# jncc3000.net
KiCad netlist of a schematic drawn in EAGLE
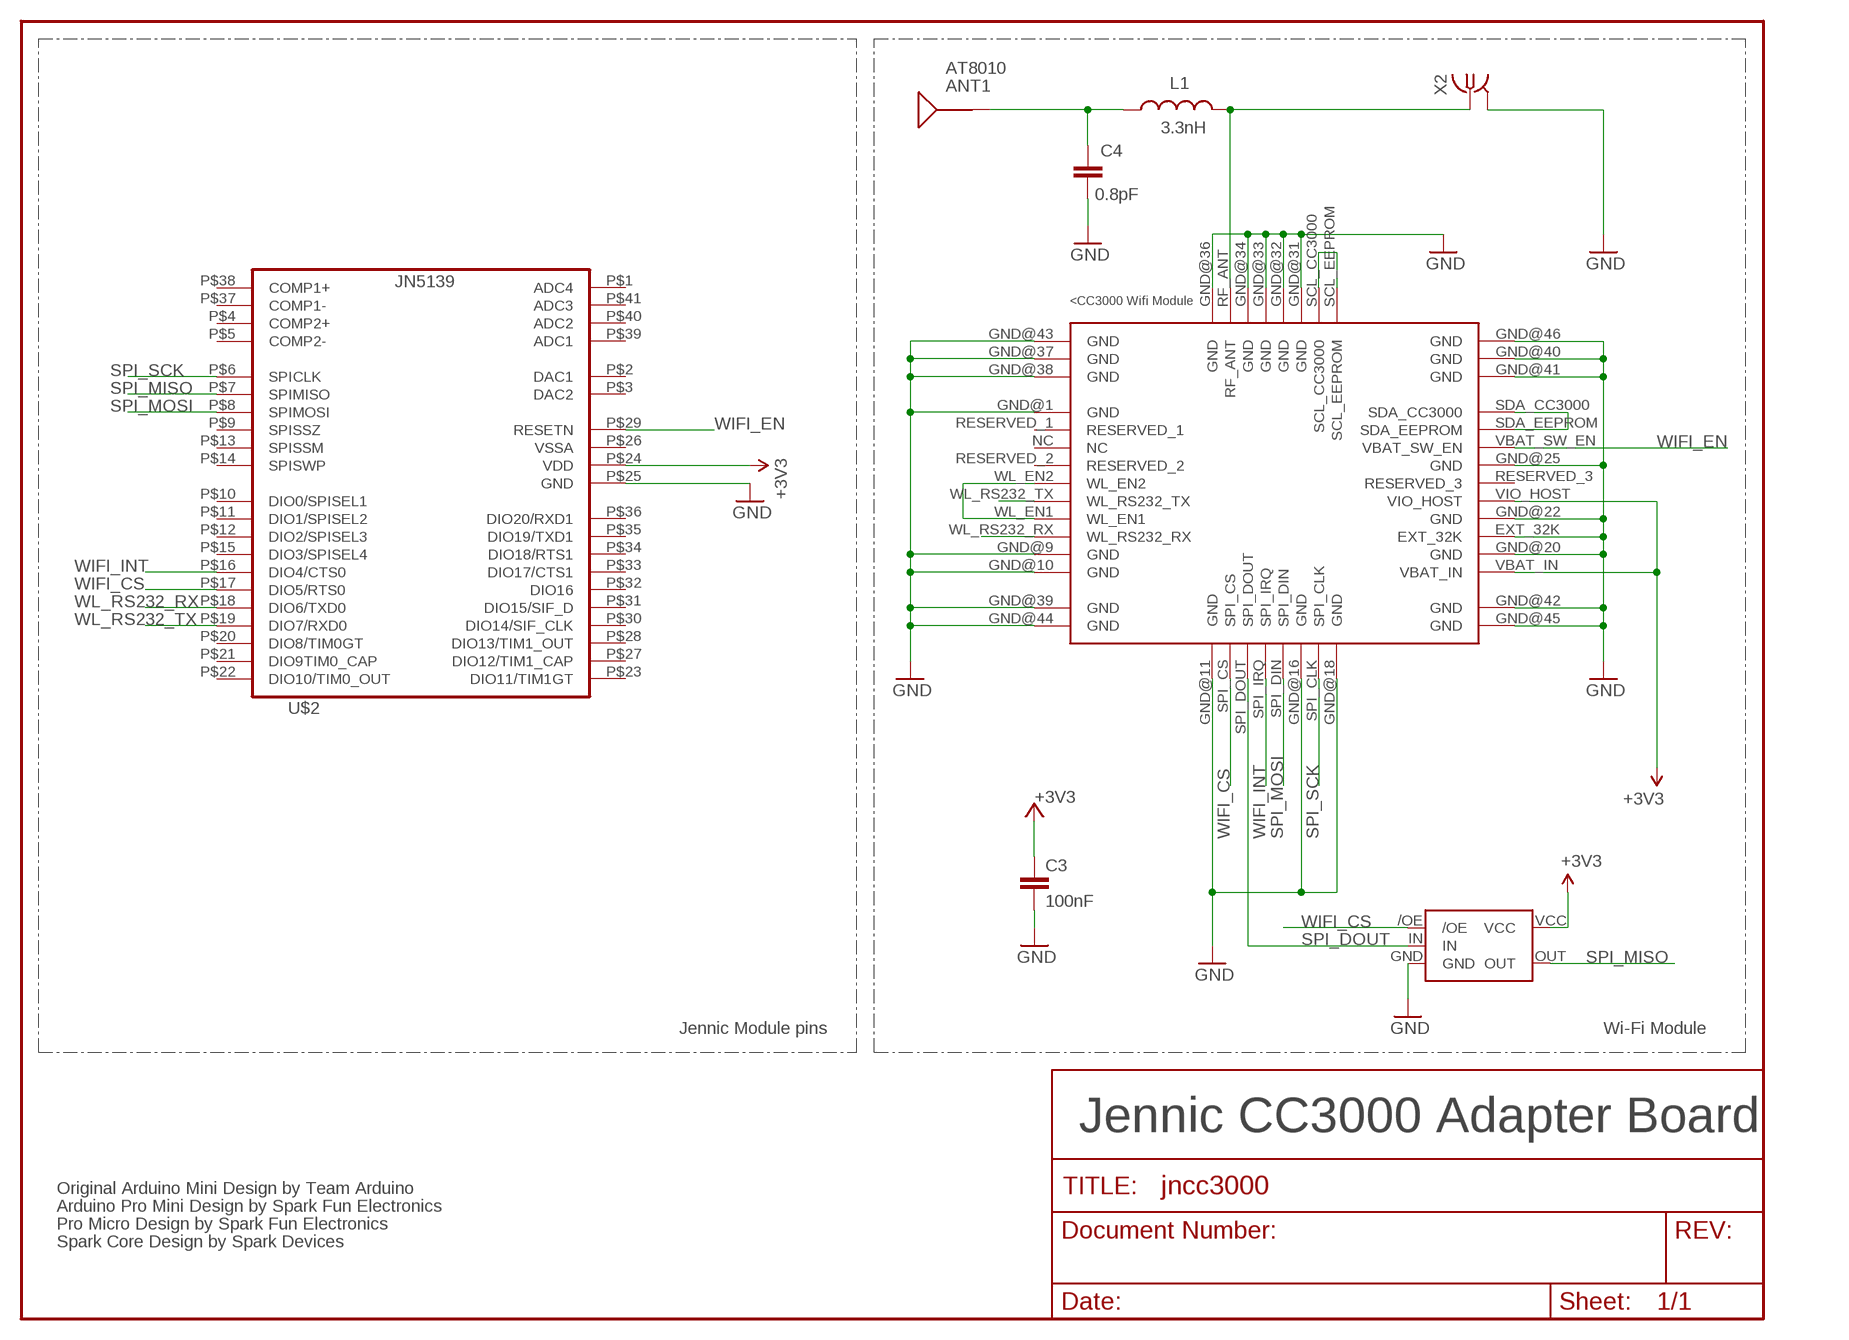
[diagram p0: schematic, sheet 1]

(export (version "E")
  (design (tool "Eeschema 10.0.6"))
  (components
    (comp (ref "ANT1")
      (value "AT8010")
      (footprint "eagle-import:AT8010")
      (libsource (lib "eagle-import") (part "AT8010"))
    )
    (comp (ref "C3")
      (value "100nF")
      (footprint "eagle-import:C0603")
      (libsource (lib "eagle-import") (part "C-EUC0603"))
    )
    (comp (ref "C4")
      (value "0.8pF")
      (footprint "eagle-import:C0603")
      (fields (field (name "COMMENT") "RF Capacitor"))
      (libsource (lib "eagle-import") (part "C-EUC0603"))
    )
    (comp (ref "L1")
      (value "3.3nH")
      (footprint "eagle-import:0603")
      (fields (field (name "COMMENT") "RF Inductor"))
      (libsource (lib "eagle-import") (part "INDUCTOR0603"))
    )
    (comp (ref "U$2")
      (value "JENNIC_JN51XXTH")
      (footprint "eagle-import:JN5139_TH")
      (libsource (lib "eagle-import") (part "JENNIC_JN51XXTH"))
    )
    (comp (ref "U1")
      (value "CC3000")
      (footprint "eagle-import:CC3000")
      (libsource (lib "eagle-import") (part "CC3000"))
    )
    (comp (ref "U4")
      (value "NL17SZ125SOT553")
      (footprint "eagle-import:SOT-553")
      (libsource (lib "eagle-import") (part "NL17SZ125SOT553"))
    )
    (comp (ref "X2")
      (value "IPEX-20279-001E")
      (footprint "eagle-import:IPEX-20279-001E")
      (libsource (lib "eagle-import") (part "IPEX-20279-001E"))
    )
  )
  (nets
    (net (code "1") (name "+3V3") (class "Default")
      (node (ref "C3") (pin "1") (pinfunction "1_1") (pintype "passive"))
      (node (ref "U$2") (pin "P$24") (pinfunction "VDD_P$24") (pintype "bidirectional"))
      (node (ref "U1") (pin "VBAT_IN") (pinfunction "VBAT_IN_VBAT_IN") (pintype "power_in"))
      (node (ref "U1") (pin "VIO_HOST") (pinfunction "VIO_HOST_VIO_HOST") (pintype "power_in"))
      (node (ref "U4") (pin "VCC") (pinfunction "VCC_VCC") (pintype "bidirectional"))
    )
    (net (code "2") (name "/SPI_DOUT") (class "Default")
      (node (ref "U1") (pin "SPI_DOUT") (pinfunction "SPI_DOUT_SPI_DOUT") (pintype "output"))
      (node (ref "U4") (pin "IN") (pinfunction "IN_IN") (pintype "bidirectional"))
    )
    (net (code "3") (name "/SPI_MISO") (class "Default")
      (node (ref "U$2") (pin "P$7") (pinfunction "SPIMISO_P$7") (pintype "bidirectional"))
      (node (ref "U4") (pin "OUT") (pinfunction "OUT_OUT") (pintype "bidirectional"))
    )
    (net (code "4") (name "/SPI_MOSI") (class "Default")
      (node (ref "U$2") (pin "P$8") (pinfunction "SPIMOSI_P$8") (pintype "bidirectional"))
      (node (ref "U1") (pin "SPI_DIN") (pinfunction "SPI_DIN_SPI_DIN") (pintype "input"))
    )
    (net (code "5") (name "/SPI_SCK") (class "Default")
      (node (ref "U$2") (pin "P$6") (pinfunction "SPICLK_P$6") (pintype "bidirectional"))
      (node (ref "U1") (pin "SPI_CLK") (pinfunction "SPI_CLK_SPI_CLK") (pintype "input"))
    )
    (net (code "6") (name "/WIFI_CS") (class "Default")
      (node (ref "U$2") (pin "P$17") (pinfunction "DIO5/RTS0_P$17") (pintype "bidirectional"))
      (node (ref "U1") (pin "SPI_CS") (pinfunction "SPI_CS_SPI_CS") (pintype "input"))
      (node (ref "U4") (pin "/OE") (pinfunction "/OE_/OE") (pintype "bidirectional"))
    )
    (net (code "7") (name "/WIFI_EN") (class "Default")
      (node (ref "U$2") (pin "P$29") (pinfunction "RESETN_P$29") (pintype "bidirectional"))
      (node (ref "U1") (pin "VBAT_SW_EN") (pinfunction "VBAT_SW_EN_VBAT_SW_EN") (pintype "input"))
    )
    (net (code "8") (name "/WIFI_INT") (class "Default")
      (node (ref "U$2") (pin "P$16") (pinfunction "DIO4/CTS0_P$16") (pintype "bidirectional"))
      (node (ref "U1") (pin "SPI_IRQ") (pinfunction "SPI_IRQ_SPI_IRQ") (pintype "output"))
    )
    (net (code "9") (name "/WL_RS232_RX") (class "Default")
      (node (ref "U$2") (pin "P$18") (pinfunction "DIO6/TXD0_P$18") (pintype "bidirectional"))
      (node (ref "U1") (pin "WL_RS232_RX") (pinfunction "WL_RS232_RX_WL_RS232_RX") (pintype "input"))
    )
    (net (code "10") (name "/WL_RS232_TX") (class "Default")
      (node (ref "U$2") (pin "P$19") (pinfunction "DIO7/RXD0_P$19") (pintype "bidirectional"))
      (node (ref "U1") (pin "WL_RS232_TX") (pinfunction "WL_RS232_TX_WL_RS232_TX") (pintype "output"))
    )
    (net (code "11") (name "GND") (class "Default")
      (node (ref "C3") (pin "2") (pinfunction "2_2") (pintype "passive"))
      (node (ref "C4") (pin "2") (pinfunction "2_2") (pintype "passive"))
      (node (ref "U$2") (pin "P$25") (pinfunction "GND_P$25") (pintype "bidirectional"))
      (node (ref "U1") (pin "EXT_32K") (pinfunction "EXT_32K_EXT_32K") (pintype "bidirectional"))
      (node (ref "U1") (pin "GND@1") (pinfunction "GND_GND@1") (pintype "power_in"))
      (node (ref "U1") (pin "GND@10") (pinfunction "GND_GND@10") (pintype "power_in"))
      (node (ref "U1") (pin "GND@11") (pinfunction "GND_GND@11") (pintype "power_in"))
      (node (ref "U1") (pin "GND@16") (pinfunction "GND_GND@16") (pintype "power_in"))
      (node (ref "U1") (pin "GND@18") (pinfunction "GND_GND@18") (pintype "power_in"))
      (node (ref "U1") (pin "GND@20") (pinfunction "GND_GND@20") (pintype "power_in"))
      (node (ref "U1") (pin "GND@22") (pinfunction "GND_GND@22") (pintype "power_in"))
      (node (ref "U1") (pin "GND@25") (pinfunction "GND_GND@25") (pintype "power_in"))
      (node (ref "U1") (pin "GND@31") (pinfunction "GND_GND@31") (pintype "power_in"))
      (node (ref "U1") (pin "GND@32") (pinfunction "GND_GND@32") (pintype "power_in"))
      (node (ref "U1") (pin "GND@33") (pinfunction "GND_GND@33") (pintype "power_in"))
      (node (ref "U1") (pin "GND@34") (pinfunction "GND_GND@34") (pintype "power_in"))
      (node (ref "U1") (pin "GND@36") (pinfunction "GND_GND@36") (pintype "power_in"))
      (node (ref "U1") (pin "GND@37") (pinfunction "GND_GND@37") (pintype "power_in"))
      (node (ref "U1") (pin "GND@38") (pinfunction "GND_GND@38") (pintype "power_in"))
      (node (ref "U1") (pin "GND@39") (pinfunction "GND_GND@39") (pintype "power_in"))
      (node (ref "U1") (pin "GND@40") (pinfunction "GND_GND@40") (pintype "power_in"))
      (node (ref "U1") (pin "GND@41") (pinfunction "GND_GND@41") (pintype "power_in"))
      (node (ref "U1") (pin "GND@42") (pinfunction "GND_GND@42") (pintype "power_in"))
      (node (ref "U1") (pin "GND@43") (pinfunction "GND_GND@43") (pintype "power_in"))
      (node (ref "U1") (pin "GND@44") (pinfunction "GND_GND@44") (pintype "power_in"))
      (node (ref "U1") (pin "GND@45") (pinfunction "GND_GND@45") (pintype "power_in"))
      (node (ref "U1") (pin "GND@46") (pinfunction "GND_GND@46") (pintype "power_in"))
      (node (ref "U1") (pin "GND@9") (pinfunction "GND_GND@9") (pintype "power_in"))
      (node (ref "U4") (pin "GND") (pinfunction "GND_GND") (pintype "bidirectional"))
      (node (ref "X2") (pin "2@1") (pinfunction "GND_2@1") (pintype "passive"))
      (node (ref "X2") (pin "2@2") (pinfunction "GND_2@2") (pintype "passive"))
    )
    (net (code "12") (name "Net-(ANT1-SIGNAL)") (class "Default")
      (node (ref "ANT1") (pin "SIG") (pinfunction "SIGNAL_SIG") (pintype "bidirectional"))
      (node (ref "C4") (pin "1") (pinfunction "1_1") (pintype "passive"))
      (node (ref "L1") (pin "1") (pinfunction "1_1") (pintype "passive"))
    )
    (net (code "13") (name "Net-(L1-Pad2)") (class "Default")
      (node (ref "L1") (pin "2") (pinfunction "2_2") (pintype "passive"))
      (node (ref "U1") (pin "RF_ANT") (pinfunction "RF_ANT_RF_ANT") (pintype "bidirectional"))
      (node (ref "X2") (pin "1") (pinfunction "1_1") (pintype "passive"))
    )
    (net (code "14") (name "Net-(U1-PadSCL_CC3000)") (class "Default")
      (node (ref "U1") (pin "SCL_CC3000") (pinfunction "SCL_CC3000_SCL_CC3000") (pintype "bidirectional"))
      (node (ref "U1") (pin "SCL_EEPROM") (pinfunction "SCL_EEPROM_SCL_EEPROM") (pintype "bidirectional"))
    )
    (net (code "15") (name "Net-(U1-PadSDA_CC3000)") (class "Default")
      (node (ref "U1") (pin "SDA_CC3000") (pinfunction "SDA_CC3000_SDA_CC3000") (pintype "bidirectional"))
      (node (ref "U1") (pin "SDA_EEPROM") (pinfunction "SDA_EEPROM_SDA_EEPROM") (pintype "bidirectional"))
    )
    (net (code "16") (name "Net-(U1-PadWL_EN1)") (class "Default")
      (node (ref "U1") (pin "WL_EN1") (pinfunction "WL_EN1_WL_EN1") (pintype "input"))
      (node (ref "U1") (pin "WL_EN2") (pinfunction "WL_EN2_WL_EN2") (pintype "input"))
    )
    (net (code "17") (name "unconnected-(U$2-ADC1-PadP$39)") (class "Default")
      (node (ref "U$2") (pin "P$39") (pinfunction "ADC1_P$39") (pintype "bidirectional"))
    )
    (net (code "18") (name "unconnected-(U$2-ADC2-PadP$40)") (class "Default")
      (node (ref "U$2") (pin "P$40") (pinfunction "ADC2_P$40") (pintype "bidirectional"))
    )
    (net (code "19") (name "unconnected-(U$2-ADC3-PadP$41)") (class "Default")
      (node (ref "U$2") (pin "P$41") (pinfunction "ADC3_P$41") (pintype "bidirectional"))
    )
    (net (code "20") (name "unconnected-(U$2-ADC4-PadP$1)") (class "Default")
      (node (ref "U$2") (pin "P$1") (pinfunction "ADC4_P$1") (pintype "bidirectional"))
    )
    (net (code "21") (name "unconnected-(U$2-COMP1+-PadP$38)") (class "Default")
      (node (ref "U$2") (pin "P$38") (pinfunction "COMP1+_P$38") (pintype "bidirectional"))
    )
    (net (code "22") (name "unconnected-(U$2-COMP1--PadP$37)") (class "Default")
      (node (ref "U$2") (pin "P$37") (pinfunction "COMP1-_P$37") (pintype "bidirectional"))
    )
    (net (code "23") (name "unconnected-(U$2-COMP2+-PadP$4)") (class "Default")
      (node (ref "U$2") (pin "P$4") (pinfunction "COMP2+_P$4") (pintype "bidirectional"))
    )
    (net (code "24") (name "unconnected-(U$2-COMP2--PadP$5)") (class "Default")
      (node (ref "U$2") (pin "P$5") (pinfunction "COMP2-_P$5") (pintype "bidirectional"))
    )
    (net (code "25") (name "unconnected-(U$2-DAC1-PadP$2)") (class "Default")
      (node (ref "U$2") (pin "P$2") (pinfunction "DAC1_P$2") (pintype "bidirectional"))
    )
    (net (code "26") (name "unconnected-(U$2-DAC2-PadP$3)") (class "Default")
      (node (ref "U$2") (pin "P$3") (pinfunction "DAC2_P$3") (pintype "bidirectional"))
    )
    (net (code "27") (name "unconnected-(U$2-DIO0{slash}SPISEL1-PadP$10)") (class "Default")
      (node (ref "U$2") (pin "P$10") (pinfunction "DIO0/SPISEL1_P$10") (pintype "bidirectional"))
    )
    (net (code "28") (name "unconnected-(U$2-DIO1{slash}SPISEL2-PadP$11)") (class "Default")
      (node (ref "U$2") (pin "P$11") (pinfunction "DIO1/SPISEL2_P$11") (pintype "bidirectional"))
    )
    (net (code "29") (name "unconnected-(U$2-DIO2{slash}SPISEL3-PadP$12)") (class "Default")
      (node (ref "U$2") (pin "P$12") (pinfunction "DIO2/SPISEL3_P$12") (pintype "bidirectional"))
    )
    (net (code "30") (name "unconnected-(U$2-DIO3{slash}SPISEL4-PadP$15)") (class "Default")
      (node (ref "U$2") (pin "P$15") (pinfunction "DIO3/SPISEL4_P$15") (pintype "bidirectional"))
    )
    (net (code "31") (name "unconnected-(U$2-DIO8{slash}TIM0GT-PadP$20)") (class "Default")
      (node (ref "U$2") (pin "P$20") (pinfunction "DIO8/TIM0GT_P$20") (pintype "bidirectional"))
    )
    (net (code "32") (name "unconnected-(U$2-DIO9TIM0_CAP-PadP$21)") (class "Default")
      (node (ref "U$2") (pin "P$21") (pinfunction "DIO9TIM0_CAP_P$21") (pintype "bidirectional"))
    )
    (net (code "33") (name "unconnected-(U$2-DIO10{slash}TIM0_OUT-PadP$22)") (class "Default")
      (node (ref "U$2") (pin "P$22") (pinfunction "DIO10/TIM0_OUT_P$22") (pintype "bidirectional"))
    )
    (net (code "34") (name "unconnected-(U$2-DIO11{slash}TIM1GT-PadP$23)") (class "Default")
      (node (ref "U$2") (pin "P$23") (pinfunction "DIO11/TIM1GT_P$23") (pintype "bidirectional"))
    )
    (net (code "35") (name "unconnected-(U$2-DIO12{slash}TIM1_CAP-PadP$27)") (class "Default")
      (node (ref "U$2") (pin "P$27") (pinfunction "DIO12/TIM1_CAP_P$27") (pintype "bidirectional"))
    )
    (net (code "36") (name "unconnected-(U$2-DIO13{slash}TIM1_OUT-PadP$28)") (class "Default")
      (node (ref "U$2") (pin "P$28") (pinfunction "DIO13/TIM1_OUT_P$28") (pintype "bidirectional"))
    )
    (net (code "37") (name "unconnected-(U$2-DIO14{slash}SIF_CLK-PadP$30)") (class "Default")
      (node (ref "U$2") (pin "P$30") (pinfunction "DIO14/SIF_CLK_P$30") (pintype "bidirectional"))
    )
    (net (code "38") (name "unconnected-(U$2-DIO15{slash}SIF_D-PadP$31)") (class "Default")
      (node (ref "U$2") (pin "P$31") (pinfunction "DIO15/SIF_D_P$31") (pintype "bidirectional"))
    )
    (net (code "39") (name "unconnected-(U$2-DIO16-PadP$32)") (class "Default")
      (node (ref "U$2") (pin "P$32") (pinfunction "DIO16_P$32") (pintype "bidirectional"))
    )
    (net (code "40") (name "unconnected-(U$2-DIO17{slash}CTS1-PadP$33)") (class "Default")
      (node (ref "U$2") (pin "P$33") (pinfunction "DIO17/CTS1_P$33") (pintype "bidirectional"))
    )
    (net (code "41") (name "unconnected-(U$2-DIO18{slash}RTS1-PadP$34)") (class "Default")
      (node (ref "U$2") (pin "P$34") (pinfunction "DIO18/RTS1_P$34") (pintype "bidirectional"))
    )
    (net (code "42") (name "unconnected-(U$2-DIO19{slash}TXD1-PadP$35)") (class "Default")
      (node (ref "U$2") (pin "P$35") (pinfunction "DIO19/TXD1_P$35") (pintype "bidirectional"))
    )
    (net (code "43") (name "unconnected-(U$2-DIO20{slash}RXD1-PadP$36)") (class "Default")
      (node (ref "U$2") (pin "P$36") (pinfunction "DIO20/RXD1_P$36") (pintype "bidirectional"))
    )
    (net (code "44") (name "unconnected-(U$2-SPISSM-PadP$13)") (class "Default")
      (node (ref "U$2") (pin "P$13") (pinfunction "SPISSM_P$13") (pintype "bidirectional"))
    )
    (net (code "45") (name "unconnected-(U$2-SPISSZ-PadP$9)") (class "Default")
      (node (ref "U$2") (pin "P$9") (pinfunction "SPISSZ_P$9") (pintype "bidirectional"))
    )
    (net (code "46") (name "unconnected-(U$2-SPISWP-PadP$14)") (class "Default")
      (node (ref "U$2") (pin "P$14") (pinfunction "SPISWP_P$14") (pintype "bidirectional"))
    )
    (net (code "47") (name "unconnected-(U$2-VSSA-PadP$26)") (class "Default")
      (node (ref "U$2") (pin "P$26") (pinfunction "VSSA_P$26") (pintype "bidirectional"))
    )
    (net (code "48") (name "unconnected-(U1-PadNC)") (class "Default")
      (node (ref "U1") (pin "NC") (pinfunction "NC_NC") (pintype "no_connect"))
    )
    (net (code "49") (name "unconnected-(U1-PadRESERVED_1)") (class "Default")
      (node (ref "U1") (pin "RESERVED_1") (pinfunction "RESERVED_1_RESERVED_1") (pintype "bidirectional"))
    )
    (net (code "50") (name "unconnected-(U1-PadRESERVED_2)") (class "Default")
      (node (ref "U1") (pin "RESERVED_2") (pinfunction "RESERVED_2_RESERVED_2") (pintype "bidirectional"))
    )
    (net (code "51") (name "unconnected-(U1-PadRESERVED_3)") (class "Default")
      (node (ref "U1") (pin "RESERVED_3") (pinfunction "RESERVED_3_RESERVED_3") (pintype "bidirectional"))
    )
  )
)
